# raspitreiber.net
KiCad netlist of a schematic drawn in EAGLE
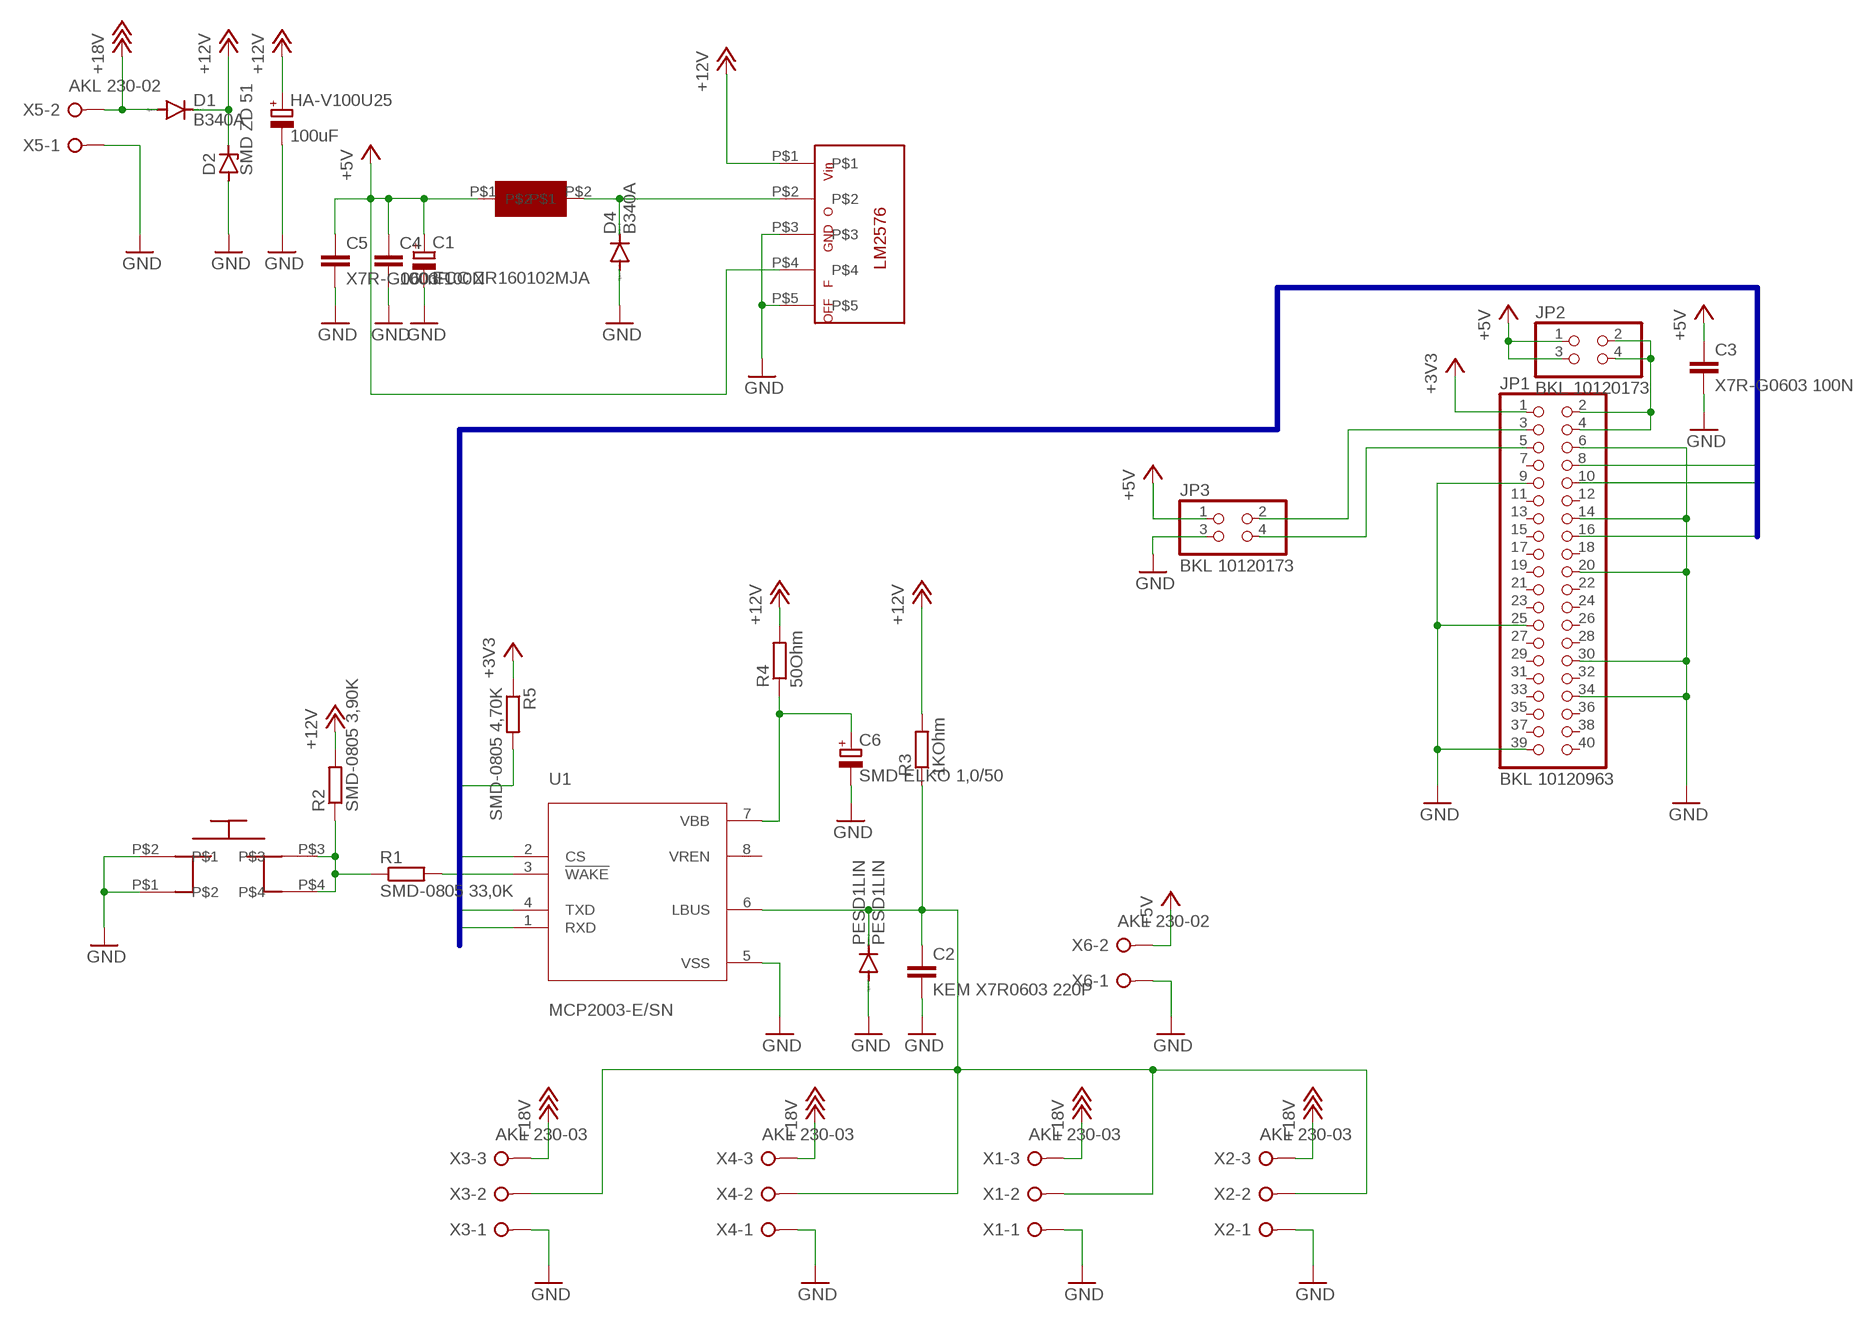
[diagram p0: schematic, sheet 1]

(export (version "E")
  (design (tool "Eeschema 10.0.6"))
  (components
    (comp (ref "C1")
      (value "ECC ZR160102MJA")
      (footprint "eagle-import:153CLV-1012")
      (libsource (lib "eagle-import") (part "CPOL-EU153CLV-1012"))
    )
    (comp (ref "C2")
      (value "KEM X7R0603 220P")
      (footprint "eagle-import:C0603")
      (libsource (lib "eagle-import") (part "C-EUC0603"))
    )
    (comp (ref "C3")
      (value "X7R-G0603 100N")
      (footprint "eagle-import:C0603")
      (libsource (lib "eagle-import") (part "C-EUC0603"))
    )
    (comp (ref "C4")
      (value "100nF")
      (footprint "eagle-import:C0603")
      (libsource (lib "eagle-import") (part "C-EUC0603"))
    )
    (comp (ref "C5")
      (value "X7R-G0603 100N")
      (footprint "eagle-import:C0603")
      (libsource (lib "eagle-import") (part "C-EUC0603"))
    )
    (comp (ref "C6")
      (value "SMD ELKO 1,0/50")
      (footprint "eagle-import:150CLZ-0810")
      (libsource (lib "eagle-import") (part "CPOL-EU150CLZ-0810"))
    )
    (comp (ref "D1")
      (value "B340A")
      (footprint "eagle-import:SMC")
      (libsource (lib "eagle-import") (part "DIODE-SMC"))
    )
    (comp (ref "D2")
      (value "SMD ZD 51")
      (footprint "eagle-import:SOT23")
      (libsource (lib "eagle-import") (part "ZENER-DIODESOT23"))
    )
    (comp (ref "D4")
      (value "B340A")
      (footprint "eagle-import:SMC")
      (libsource (lib "eagle-import") (part "DIODE-SMC"))
    )
    (comp (ref "HA-V100U25")
      (value "100uF")
      (footprint "eagle-import:153CLV-0807")
      (libsource (lib "eagle-import") (part "CPOL-EU153CLV-0807"))
    )
    (comp (ref "JP1")
      (value "BKL 10120963")
      (footprint "eagle-import:2X20")
      (libsource (lib "eagle-import") (part "PINHD-2X20"))
    )
    (comp (ref "JP2")
      (value "BKL 10120173")
      (footprint "eagle-import:2X02")
      (libsource (lib "eagle-import") (part "PINHD-2X2"))
    )
    (comp (ref "JP3")
      (value "BKL 10120173")
      (footprint "eagle-import:2X02")
      (libsource (lib "eagle-import") (part "PINHD-2X2"))
    )
    (comp (ref "L-09HVP100")
      (value "LDEVICE7MM")
      (footprint "eagle-import:LFOOT7MM")
      (libsource (lib "eagle-import") (part "LDEVICE7MM"))
    )
    (comp (ref "PESD1LIN")
      (value "PESD1LIN")
      (footprint "eagle-import:SOD323-W")
      (libsource (lib "eagle-import") (part "DIODE-SOD323-W"))
    )
    (comp (ref "R1")
      (value "SMD-0805 33,0K")
      (footprint "eagle-import:M0805")
      (libsource (lib "eagle-import") (part "R-EU_M0805"))
    )
    (comp (ref "R2")
      (value "SMD-0805 3,90K")
      (footprint "eagle-import:M0805")
      (libsource (lib "eagle-import") (part "R-EU_M0805"))
    )
    (comp (ref "R3")
      (value "1KOhm")
      (footprint "eagle-import:M0805")
      (libsource (lib "eagle-import") (part "R-EU_M0805"))
    )
    (comp (ref "R4")
      (value "50Ohm")
      (footprint "eagle-import:M0805")
      (libsource (lib "eagle-import") (part "R-EU_M0805"))
    )
    (comp (ref "R5")
      (value "SMD-0805 4,70K")
      (footprint "eagle-import:M0805")
      (libsource (lib "eagle-import") (part "R-EU_M0805"))
    )
    (comp (ref "TASTER9313")
      (value "SCHALTDEV")
      (footprint "eagle-import:SCHALTFOOT")
      (libsource (lib "eagle-import") (part "SCHALTDEV"))
    )
    (comp (ref "U$1")
      (value "LM2576")
      (footprint "eagle-import:LM2576")
      (libsource (lib "eagle-import") (part "LM2576"))
    )
    (comp (ref "U1")
      (value "MCP2003-E/SN")
      (footprint "eagle-import:SOIC127P600X175-8N")
      (fields (field (name "MANUFACTURER") "Microchip"))
      (libsource (lib "eagle-import") (part "MCP2003-E/SN"))
    )
    (comp (ref "X1")
      (value "AKL 230-03")
      (footprint "eagle-import:W237-3E")
      (libsource (lib "eagle-import") (part "W237-3E"))
    )
    (comp (ref "X2")
      (value "AKL 230-03")
      (footprint "eagle-import:W237-3E")
      (libsource (lib "eagle-import") (part "W237-3E"))
    )
    (comp (ref "X3")
      (value "AKL 230-03")
      (footprint "eagle-import:W237-3E")
      (libsource (lib "eagle-import") (part "W237-3E"))
    )
    (comp (ref "X4")
      (value "AKL 230-03")
      (footprint "eagle-import:W237-3E")
      (libsource (lib "eagle-import") (part "W237-3E"))
    )
    (comp (ref "X5")
      (value "AKL 230-02")
      (footprint "eagle-import:W237-132")
      (libsource (lib "eagle-import") (part "W237-02P"))
    )
    (comp (ref "X6")
      (value "AKL 230-02")
      (footprint "eagle-import:W237-132")
      (libsource (lib "eagle-import") (part "W237-02P"))
    )
  )
  (nets
    (net (code "1") (name "+3V3") (class "Default")
      (node (ref "JP1") (pin "1") (pinfunction "1_1") (pintype "passive"))
      (node (ref "R5") (pin "1") (pinfunction "1_1") (pintype "passive"))
    )
    (net (code "2") (name "+5V") (class "Default")
      (node (ref "C1") (pin "+") (pinfunction "+_+") (pintype "passive"))
      (node (ref "C3") (pin "1") (pinfunction "1_1") (pintype "passive"))
      (node (ref "C4") (pin "1") (pinfunction "1_1") (pintype "passive"))
      (node (ref "C5") (pin "1") (pinfunction "1_1") (pintype "passive"))
      (node (ref "JP2") (pin "1") (pinfunction "1_1") (pintype "passive"))
      (node (ref "JP2") (pin "3") (pinfunction "3_3") (pintype "passive"))
      (node (ref "JP3") (pin "1") (pinfunction "1_1") (pintype "passive"))
      (node (ref "L-09HVP100") (pin "P$1") (pinfunction "P$1_P$1") (pintype "bidirectional"))
      (node (ref "U$1") (pin "P$4") (pinfunction "P$4_P$4") (pintype "bidirectional"))
      (node (ref "X6") (pin "2") (pinfunction "KL_2") (pintype "passive"))
    )
    (net (code "3") (name "+12V") (class "Default")
      (node (ref "D1") (pin "C") (pinfunction "C_C") (pintype "passive"))
      (node (ref "D2") (pin "3") (pinfunction "C_3") (pintype "passive"))
      (node (ref "HA-V100U25") (pin "+") (pinfunction "+_+") (pintype "passive"))
      (node (ref "R2") (pin "2") (pinfunction "2_2") (pintype "passive"))
      (node (ref "R3") (pin "2") (pinfunction "2_2") (pintype "passive"))
      (node (ref "R4") (pin "2") (pinfunction "2_2") (pintype "passive"))
      (node (ref "U$1") (pin "P$1") (pinfunction "P$1_P$1") (pintype "bidirectional"))
    )
    (net (code "4") (name "+18V") (class "Default")
      (node (ref "D1") (pin "A") (pinfunction "A_A") (pintype "passive"))
      (node (ref "X1") (pin "3") (pinfunction "KL_3") (pintype "passive"))
      (node (ref "X2") (pin "3") (pinfunction "KL_3") (pintype "passive"))
      (node (ref "X3") (pin "3") (pinfunction "KL_3") (pintype "passive"))
      (node (ref "X4") (pin "3") (pinfunction "KL_3") (pintype "passive"))
      (node (ref "X5") (pin "2") (pinfunction "KL_2") (pintype "passive"))
    )
    (net (code "5") (name "/CS") (class "Default")
      (node (ref "JP1") (pin "16") (pinfunction "16_16") (pintype "passive"))
      (node (ref "U1") (pin "2") (pinfunction "CS_2") (pintype "input"))
    )
    (net (code "6") (name "/RX") (class "Default")
      (node (ref "JP1") (pin "10") (pinfunction "10_10") (pintype "passive"))
      (node (ref "R5") (pin "2") (pinfunction "2_2") (pintype "passive"))
      (node (ref "U1") (pin "1") (pinfunction "RXD_1") (pintype "output"))
    )
    (net (code "7") (name "/TX") (class "Default")
      (node (ref "JP1") (pin "8") (pinfunction "8_8") (pintype "passive"))
      (node (ref "U1") (pin "4") (pinfunction "TXD_4") (pintype "input"))
    )
    (net (code "8") (name "GND") (class "Default")
      (node (ref "C1") (pin "-") (pinfunction "-_-") (pintype "passive"))
      (node (ref "C2") (pin "2") (pinfunction "2_2") (pintype "passive"))
      (node (ref "C3") (pin "2") (pinfunction "2_2") (pintype "passive"))
      (node (ref "C4") (pin "2") (pinfunction "2_2") (pintype "passive"))
      (node (ref "C5") (pin "2") (pinfunction "2_2") (pintype "passive"))
      (node (ref "C6") (pin "-") (pinfunction "-_-") (pintype "passive"))
      (node (ref "D2") (pin "1") (pinfunction "A_1") (pintype "passive"))
      (node (ref "D4") (pin "A") (pinfunction "A_A") (pintype "passive"))
      (node (ref "HA-V100U25") (pin "-") (pinfunction "-_-") (pintype "passive"))
      (node (ref "JP1") (pin "14") (pinfunction "14_14") (pintype "passive"))
      (node (ref "JP1") (pin "20") (pinfunction "20_20") (pintype "passive"))
      (node (ref "JP1") (pin "25") (pinfunction "25_25") (pintype "passive"))
      (node (ref "JP1") (pin "30") (pinfunction "30_30") (pintype "passive"))
      (node (ref "JP1") (pin "34") (pinfunction "34_34") (pintype "passive"))
      (node (ref "JP1") (pin "39") (pinfunction "39_39") (pintype "passive"))
      (node (ref "JP1") (pin "6") (pinfunction "6_6") (pintype "passive"))
      (node (ref "JP1") (pin "9") (pinfunction "9_9") (pintype "passive"))
      (node (ref "JP3") (pin "3") (pinfunction "3_3") (pintype "passive"))
      (node (ref "PESD1LIN") (pin "A") (pinfunction "A_A") (pintype "passive"))
      (node (ref "TASTER9313") (pin "P$1") (pinfunction "P$2_P$1") (pintype "bidirectional"))
      (node (ref "TASTER9313") (pin "P$2") (pinfunction "P$1_P$2") (pintype "bidirectional"))
      (node (ref "U$1") (pin "P$3") (pinfunction "P$3_P$3") (pintype "bidirectional"))
      (node (ref "U$1") (pin "P$5") (pinfunction "P$5_P$5") (pintype "bidirectional"))
      (node (ref "U1") (pin "5") (pinfunction "VSS_5") (pintype "power_in"))
      (node (ref "X1") (pin "1") (pinfunction "KL_1") (pintype "passive"))
      (node (ref "X2") (pin "1") (pinfunction "KL_1") (pintype "passive"))
      (node (ref "X3") (pin "1") (pinfunction "KL_1") (pintype "passive"))
      (node (ref "X4") (pin "1") (pinfunction "KL_1") (pintype "passive"))
      (node (ref "X5") (pin "1") (pinfunction "KL_1") (pintype "passive"))
      (node (ref "X6") (pin "1") (pinfunction "KL_1") (pintype "passive"))
    )
    (net (code "9") (name "Net-(D4-PadC)") (class "Default")
      (node (ref "D4") (pin "C") (pinfunction "C_C") (pintype "passive"))
      (node (ref "L-09HVP100") (pin "P$2") (pinfunction "P$2_P$2") (pintype "bidirectional"))
      (node (ref "U$1") (pin "P$2") (pinfunction "P$2_P$2") (pintype "bidirectional"))
    )
    (net (code "10") (name "Net-(JP1-Pad2)") (class "Default")
      (node (ref "JP1") (pin "2") (pinfunction "2_2") (pintype "passive"))
      (node (ref "JP1") (pin "4") (pinfunction "4_4") (pintype "passive"))
      (node (ref "JP2") (pin "2") (pinfunction "2_2") (pintype "passive"))
      (node (ref "JP2") (pin "4") (pinfunction "4_4") (pintype "passive"))
    )
    (net (code "11") (name "Net-(JP1-Pad3)") (class "Default")
      (node (ref "JP1") (pin "3") (pinfunction "3_3") (pintype "passive"))
      (node (ref "JP3") (pin "2") (pinfunction "2_2") (pintype "passive"))
    )
    (net (code "12") (name "Net-(JP1-Pad5)") (class "Default")
      (node (ref "JP1") (pin "5") (pinfunction "5_5") (pintype "passive"))
      (node (ref "JP3") (pin "4") (pinfunction "4_4") (pintype "passive"))
    )
    (net (code "13") (name "Net-(R1-Pad1)") (class "Default")
      (node (ref "R1") (pin "1") (pinfunction "1_1") (pintype "passive"))
      (node (ref "R2") (pin "1") (pinfunction "1_1") (pintype "passive"))
      (node (ref "TASTER9313") (pin "P$3") (pinfunction "P$3_P$3") (pintype "bidirectional"))
      (node (ref "TASTER9313") (pin "P$4") (pinfunction "P$4_P$4") (pintype "bidirectional"))
    )
    (net (code "14") (name "Net-(U1-LBUS)") (class "Default")
      (node (ref "C2") (pin "1") (pinfunction "1_1") (pintype "passive"))
      (node (ref "PESD1LIN") (pin "C") (pinfunction "C_C") (pintype "passive"))
      (node (ref "R3") (pin "1") (pinfunction "1_1") (pintype "passive"))
      (node (ref "U1") (pin "6") (pinfunction "LBUS_6") (pintype "bidirectional"))
      (node (ref "X1") (pin "2") (pinfunction "KL_2") (pintype "passive"))
      (node (ref "X2") (pin "2") (pinfunction "KL_2") (pintype "passive"))
      (node (ref "X3") (pin "2") (pinfunction "KL_2") (pintype "passive"))
      (node (ref "X4") (pin "2") (pinfunction "KL_2") (pintype "passive"))
    )
    (net (code "15") (name "Net-(U1-VBB)") (class "Default")
      (node (ref "C6") (pin "+") (pinfunction "+_+") (pintype "passive"))
      (node (ref "R4") (pin "1") (pinfunction "1_1") (pintype "passive"))
      (node (ref "U1") (pin "7") (pinfunction "VBB_7") (pintype "power_in"))
    )
    (net (code "16") (name "Net-(U1-~{WAKE})") (class "Default")
      (node (ref "R1") (pin "2") (pinfunction "2_2") (pintype "passive"))
      (node (ref "U1") (pin "3") (pinfunction "~{WAKE}_3") (pintype "input"))
    )
    (net (code "17") (name "unconnected-(JP1-Pad7)") (class "Default")
      (node (ref "JP1") (pin "7") (pinfunction "7_7") (pintype "passive"))
    )
    (net (code "18") (name "unconnected-(JP1-Pad11)") (class "Default")
      (node (ref "JP1") (pin "11") (pinfunction "11_11") (pintype "passive"))
    )
    (net (code "19") (name "unconnected-(JP1-Pad12)") (class "Default")
      (node (ref "JP1") (pin "12") (pinfunction "12_12") (pintype "passive"))
    )
    (net (code "20") (name "unconnected-(JP1-Pad13)") (class "Default")
      (node (ref "JP1") (pin "13") (pinfunction "13_13") (pintype "passive"))
    )
    (net (code "21") (name "unconnected-(JP1-Pad15)") (class "Default")
      (node (ref "JP1") (pin "15") (pinfunction "15_15") (pintype "passive"))
    )
    (net (code "22") (name "unconnected-(JP1-Pad17)") (class "Default")
      (node (ref "JP1") (pin "17") (pinfunction "17_17") (pintype "passive"))
    )
    (net (code "23") (name "unconnected-(JP1-Pad18)") (class "Default")
      (node (ref "JP1") (pin "18") (pinfunction "18_18") (pintype "passive"))
    )
    (net (code "24") (name "unconnected-(JP1-Pad19)") (class "Default")
      (node (ref "JP1") (pin "19") (pinfunction "19_19") (pintype "passive"))
    )
    (net (code "25") (name "unconnected-(JP1-Pad21)") (class "Default")
      (node (ref "JP1") (pin "21") (pinfunction "21_21") (pintype "passive"))
    )
    (net (code "26") (name "unconnected-(JP1-Pad22)") (class "Default")
      (node (ref "JP1") (pin "22") (pinfunction "22_22") (pintype "passive"))
    )
    (net (code "27") (name "unconnected-(JP1-Pad23)") (class "Default")
      (node (ref "JP1") (pin "23") (pinfunction "23_23") (pintype "passive"))
    )
    (net (code "28") (name "unconnected-(JP1-Pad24)") (class "Default")
      (node (ref "JP1") (pin "24") (pinfunction "24_24") (pintype "passive"))
    )
    (net (code "29") (name "unconnected-(JP1-Pad26)") (class "Default")
      (node (ref "JP1") (pin "26") (pinfunction "26_26") (pintype "passive"))
    )
    (net (code "30") (name "unconnected-(JP1-Pad27)") (class "Default")
      (node (ref "JP1") (pin "27") (pinfunction "27_27") (pintype "passive"))
    )
    (net (code "31") (name "unconnected-(JP1-Pad28)") (class "Default")
      (node (ref "JP1") (pin "28") (pinfunction "28_28") (pintype "passive"))
    )
    (net (code "32") (name "unconnected-(JP1-Pad29)") (class "Default")
      (node (ref "JP1") (pin "29") (pinfunction "29_29") (pintype "passive"))
    )
    (net (code "33") (name "unconnected-(JP1-Pad31)") (class "Default")
      (node (ref "JP1") (pin "31") (pinfunction "31_31") (pintype "passive"))
    )
    (net (code "34") (name "unconnected-(JP1-Pad32)") (class "Default")
      (node (ref "JP1") (pin "32") (pinfunction "32_32") (pintype "passive"))
    )
    (net (code "35") (name "unconnected-(JP1-Pad33)") (class "Default")
      (node (ref "JP1") (pin "33") (pinfunction "33_33") (pintype "passive"))
    )
    (net (code "36") (name "unconnected-(JP1-Pad35)") (class "Default")
      (node (ref "JP1") (pin "35") (pinfunction "35_35") (pintype "passive"))
    )
    (net (code "37") (name "unconnected-(JP1-Pad36)") (class "Default")
      (node (ref "JP1") (pin "36") (pinfunction "36_36") (pintype "passive"))
    )
    (net (code "38") (name "unconnected-(JP1-Pad37)") (class "Default")
      (node (ref "JP1") (pin "37") (pinfunction "37_37") (pintype "passive"))
    )
    (net (code "39") (name "unconnected-(JP1-Pad38)") (class "Default")
      (node (ref "JP1") (pin "38") (pinfunction "38_38") (pintype "passive"))
    )
    (net (code "40") (name "unconnected-(JP1-Pad40)") (class "Default")
      (node (ref "JP1") (pin "40") (pinfunction "40_40") (pintype "passive"))
    )
    (net (code "41") (name "unconnected-(U1-VREN-Pad8)") (class "Default")
      (node (ref "U1") (pin "8") (pinfunction "VREN_8") (pintype "output"))
    )
  )
)
